# Sheet1.net
KiCad netlist of a schematic drawn in Altium Designer
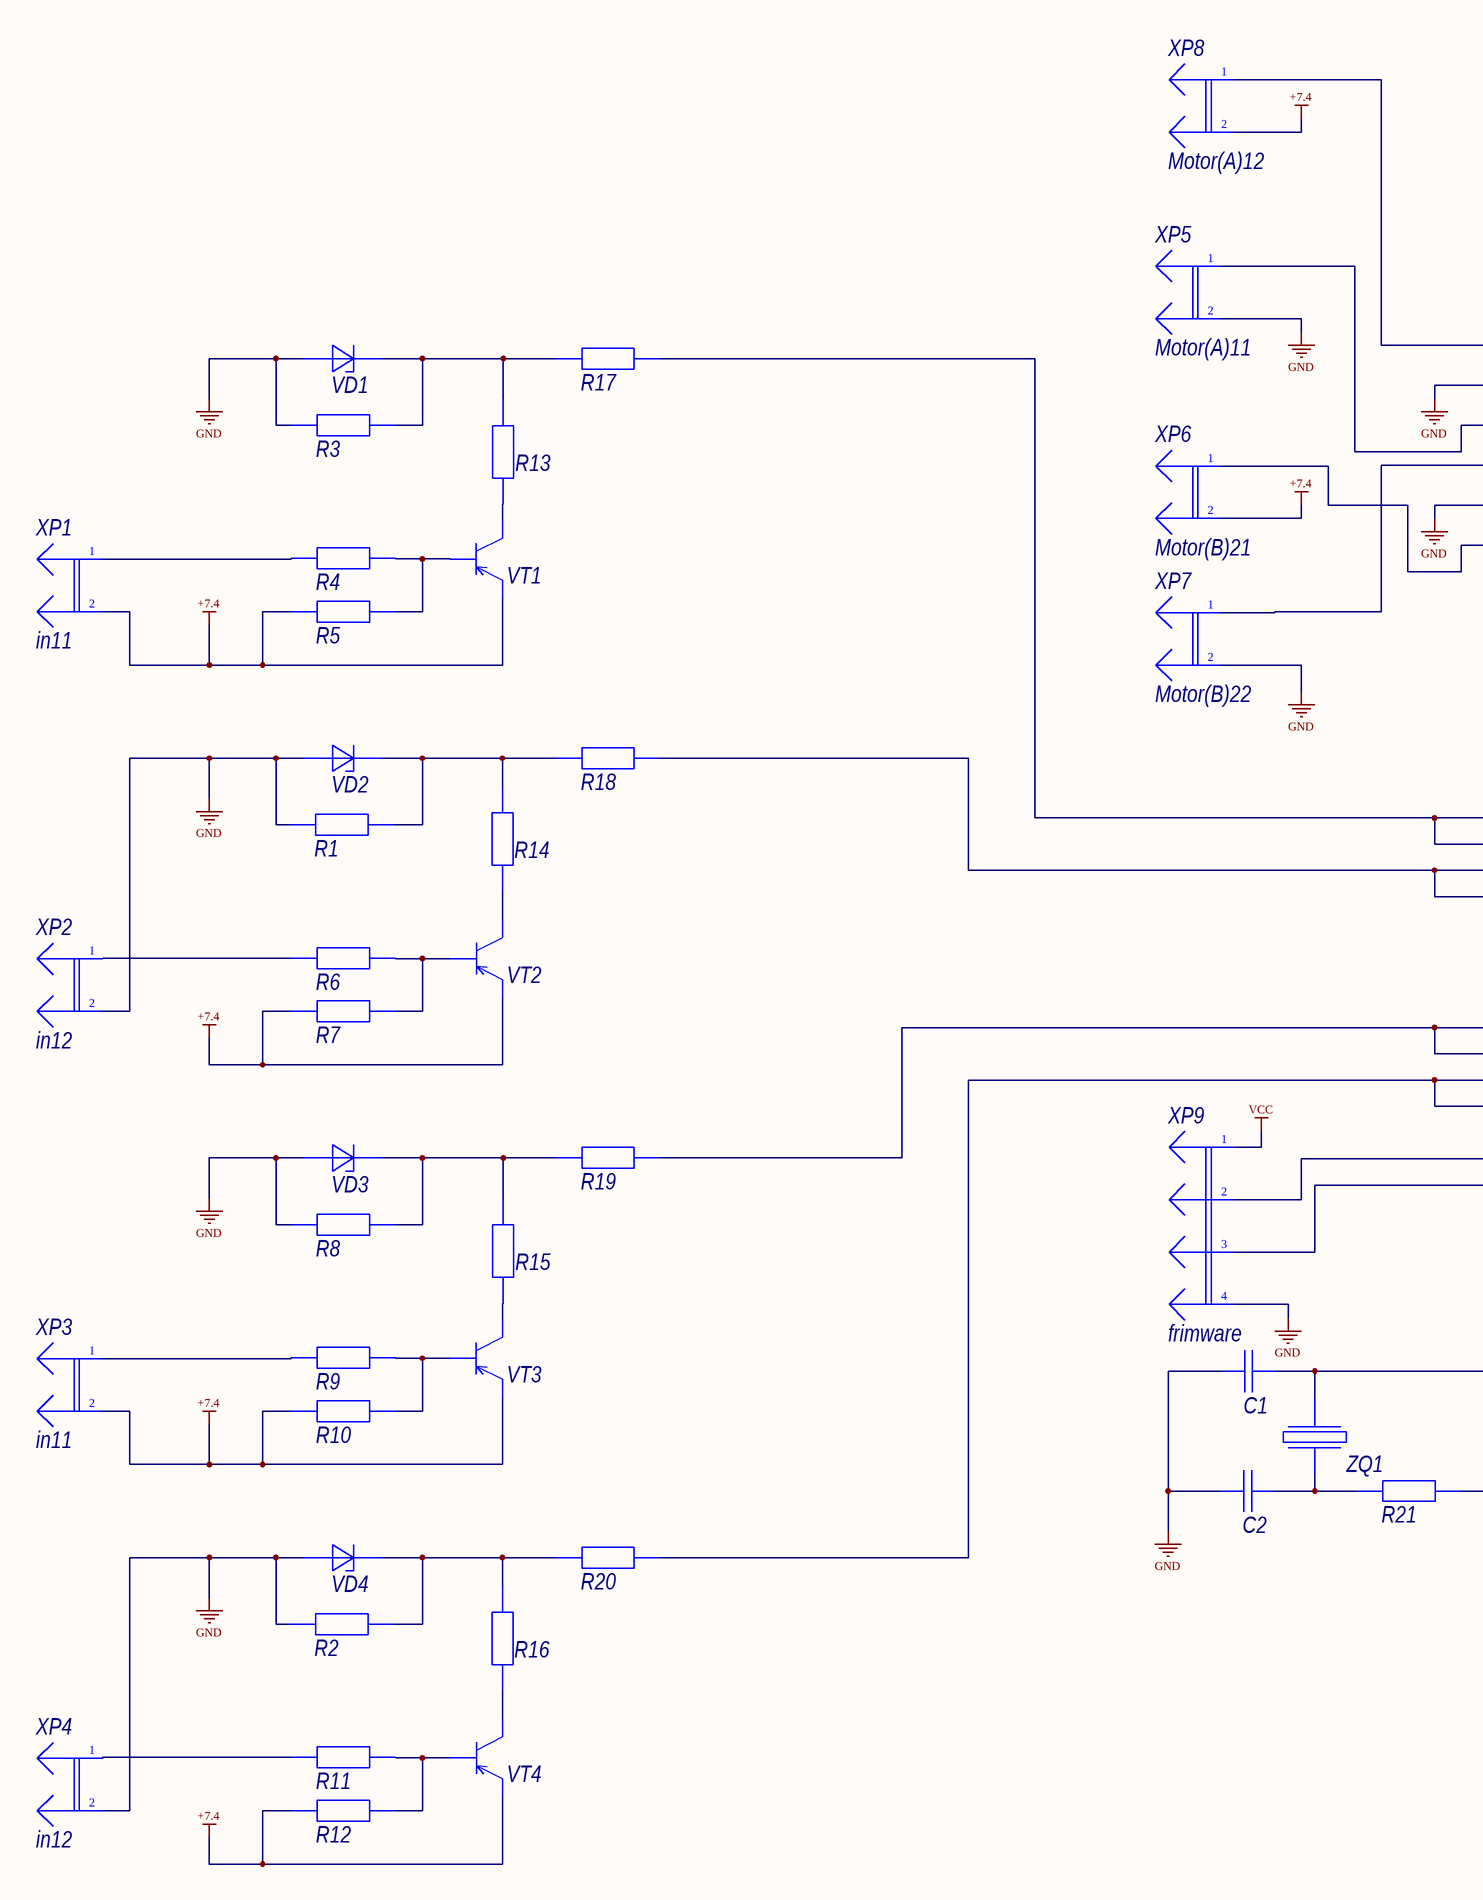
[diagram p0: Sheet1.SchDoc, left]
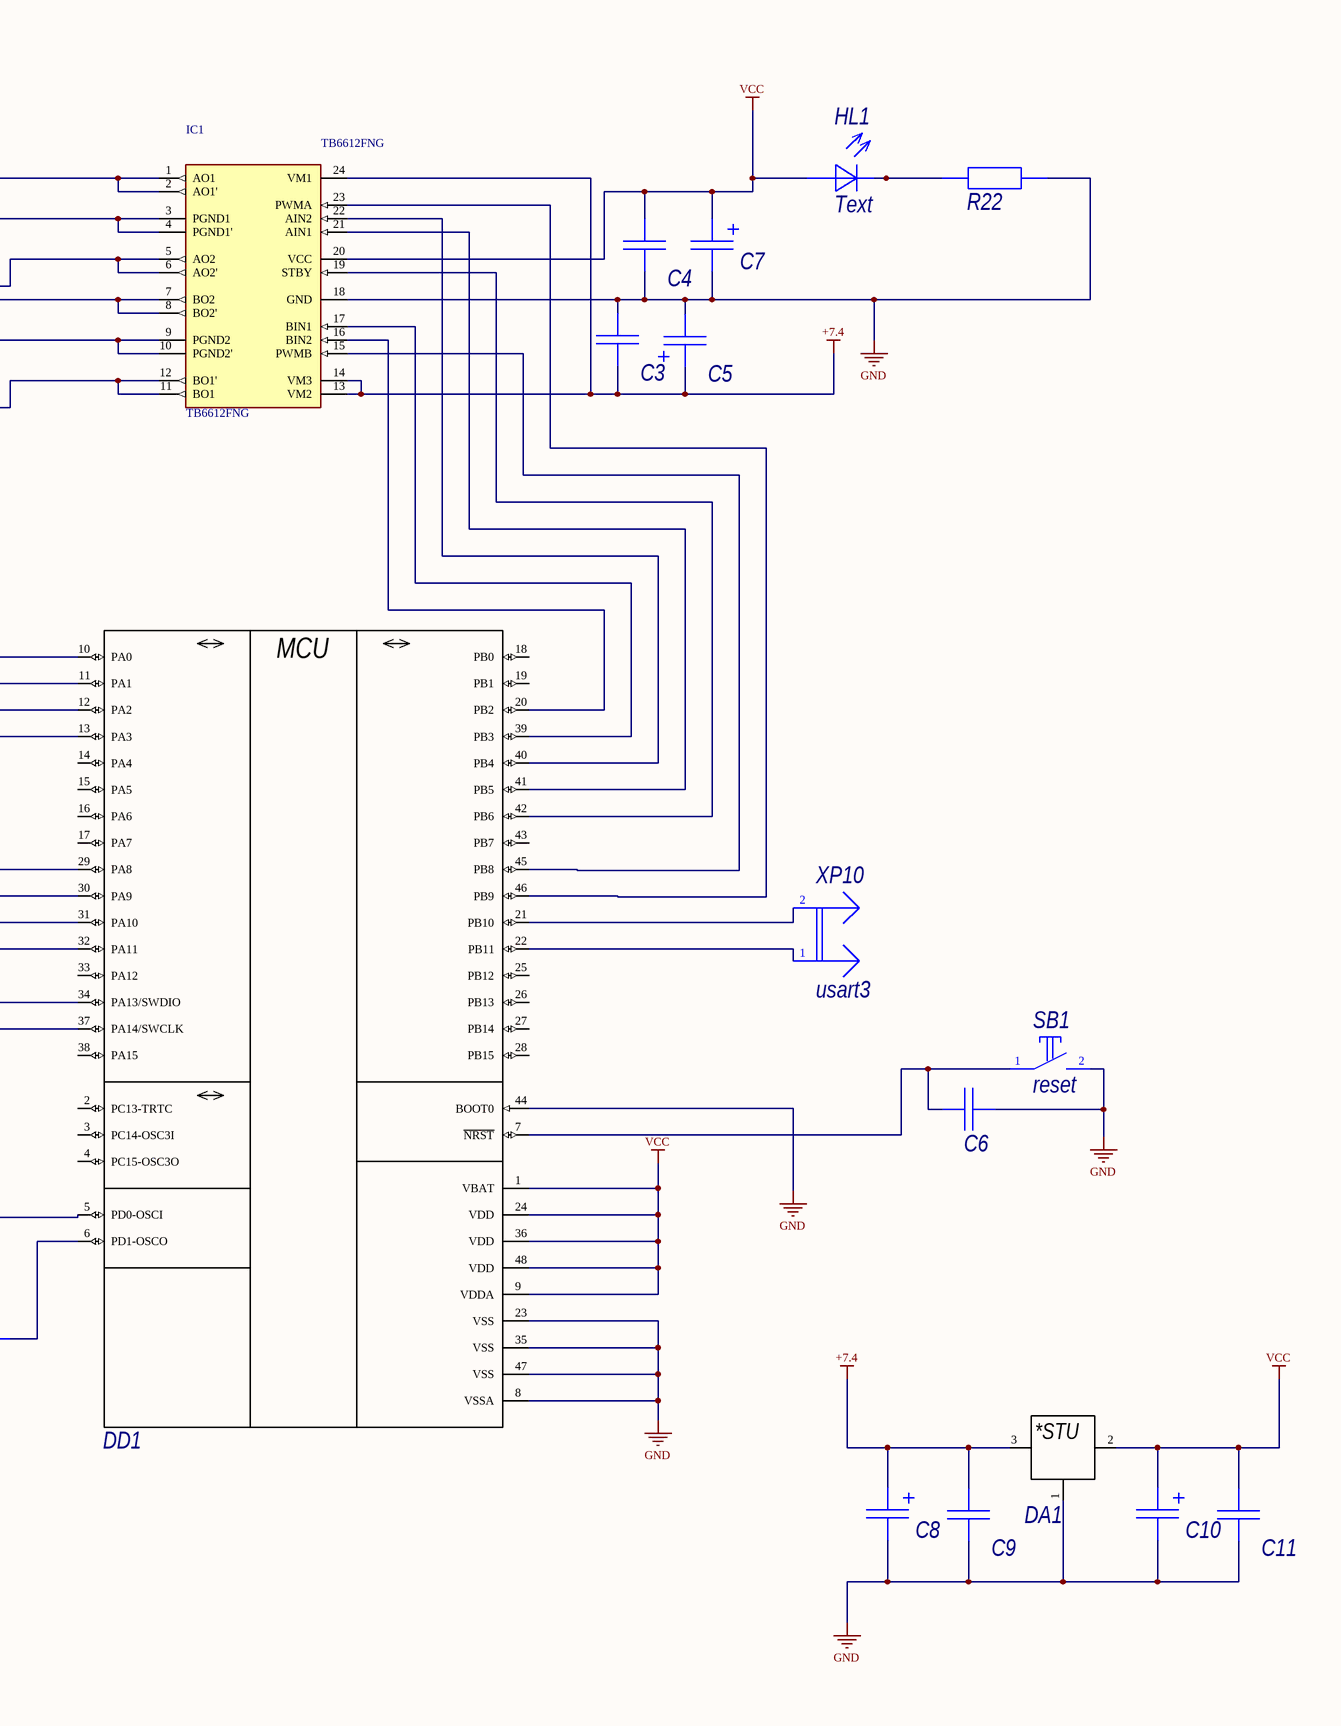
[diagram p1: Sheet1.SchDoc, right]

(export (version "E")
  (design (tool "Eeschema 10.0.6"))
  (components
    (comp (ref "C1")
      (value "Capacitor")
      (footprint "C0603")
      (description "30pF 0603")
      (fields
        (field (name "PART NUMBER") "GRM1885C1H300FA01D")
        (field (name "VOLTAGE") "50V")
        (field (name "PUBLISHER") "Andrew Danich")
      )
      (libsource (lib "Lib_IMP_GOST") (part "Capacitor"))
    )
    (comp (ref "C2")
      (value "Capacitor")
      (footprint "C0603")
      (description "30pF 0603")
      (fields
        (field (name "PART NUMBER") "GRM1885C1H300FA01D")
        (field (name "VOLTAGE") "50V")
        (field (name "PUBLISHER") "Andrew Danich")
      )
      (libsource (lib "Lib_IMP_GOST") (part "Capacitor"))
    )
    (comp (ref "C3")
      (value "Capacitor")
      (footprint "C0603")
      (description "0.1 uF")
      (fields
        (field (name "PART NUMBER") "GRM188R71C104KA01D")
        (field (name "VOLTAGE") "16V")
        (field (name "PUBLISHER") "Andrew Danich")
      )
      (libsource (lib "Lib_IMP_GOST") (part "Capacitor"))
    )
    (comp (ref "C4")
      (value "Capacitor")
      (footprint "C0603")
      (description "0.1 uF")
      (fields
        (field (name "PART NUMBER") "GRM188R71C104KA01D")
        (field (name "VOLTAGE") "16V")
        (field (name "PUBLISHER") "Andrew Danich")
      )
      (libsource (lib "Lib_IMP_GOST") (part "Capacitor"))
    )
    (comp (ref "C5")
      (value "Capacitor-T")
      (footprint "C3216-p")
      (description "10 uF")
      (fields
        (field (name "PART NUMBER") "T491A106K006AT")
        (field (name "VOLTAGE") "6.3V")
        (field (name "PUBLISHER") "Andrew Danich")
      )
      (libsource (lib "Lib_IMP_GOST") (part "Capacitor-T"))
    )
    (comp (ref "C6")
      (value "Capacitor")
      (footprint "C0603")
      (description "0.1 uF 0603")
      (fields
        (field (name "PART NUMBER") "GRM188R71C104KA01D")
        (field (name "VOLTAGE") "16V")
        (field (name "PUBLISHER") "Andrew Danich")
      )
      (libsource (lib "Lib_IMP_GOST") (part "Capacitor"))
    )
    (comp (ref "C7")
      (value "Capacitor-T")
      (footprint "C3216-p")
      (description "10 uF")
      (fields
        (field (name "PART NUMBER") "T491A106K006AT")
        (field (name "VOLTAGE") "6.3V")
        (field (name "PUBLISHER") "Andrew Danich")
      )
      (libsource (lib "Lib_IMP_GOST") (part "Capacitor-T"))
    )
    (comp (ref "C8")
      (value "Capacitor-T")
      (footprint "C3216-p")
      (description "10 uF")
      (fields
        (field (name "PART NUMBER") "T491A106K006AT")
        (field (name "VOLTAGE") "6.3V")
        (field (name "PUBLISHER") "Andrew Danich")
      )
      (libsource (lib "Lib_IMP_GOST") (part "Capacitor-T"))
    )
    (comp (ref "C9")
      (value "Capacitor")
      (footprint "C0603")
      (description "0.1 uF")
      (fields
        (field (name "PART NUMBER") "GRM188R71C104KA01D")
        (field (name "VOLTAGE") "16V")
        (field (name "PUBLISHER") "Andrew Danich")
      )
      (libsource (lib "Lib_IMP_GOST") (part "Capacitor"))
    )
    (comp (ref "C10")
      (value "Capacitor-T")
      (footprint "C3216-p")
      (description "10 uF")
      (fields
        (field (name "PART NUMBER") "T491A106K006AT")
        (field (name "VOLTAGE") "6.3V")
        (field (name "PUBLISHER") "Andrew Danich")
      )
      (libsource (lib "Lib_IMP_GOST") (part "Capacitor-T"))
    )
    (comp (ref "C11")
      (value "Capacitor")
      (footprint "C0603")
      (description "0.1 uF")
      (fields
        (field (name "PART NUMBER") "GRM188R71C104KA01D")
        (field (name "VOLTAGE") "16V")
        (field (name "PUBLISHER") "Andrew Danich")
      )
      (libsource (lib "Lib_IMP_GOST") (part "Capacitor"))
    )
    (comp (ref "DA1")
      (value "LM1117-Series")
      (footprint "SOT-223")
      (fields (field (name "PART NUMBER") "LM1117MPX-ADJ") (field (name "PUBLISHER") "Andrew Danich"))
      (libsource (lib "Lib_IMP_GOST") (part "LM1117-Series"))
    )
    (comp (ref "DD1")
      (value "STM32F103Cxxx-Series")
      (footprint "LQFP-48")
      (fields
        (field (name "PART NUMBER") "STM32F103C8T6")
        (field (name "MANUFACTURER") "STMicroelectronics")
        (field (name "PUBLISHER") "Andrew Danich")
      )
      (libsource (lib "Lib_IMP_GOST") (part "STM32F103Cxxx-Series"))
    )
    (comp (ref "HL1")
      (value "Text")
      (footprint "LD0805")
      (fields
        (field (name "PART NUMBER") "KP-2012SGC")
        (field (name "MANUFACTURER") "Kingbright")
        (field (name "PUBLISHER") "Andrew Danich")
      )
      (libsource (lib "Lib_IMP_GOST") (part "Led-1"))
    )
    (comp (ref "IC1")
      (value "TB6612FNG")
      (footprint "SSOP24")
      (description "Motor Driver Power MOSFET Parallel 24-SSOP")
      (fields (field (name "MF") "Toshiba"))
      (libsource (lib "TB6612FNG") (part "TB6612FNG"))
    )
    (comp (ref "R1")
      (value "Resistor")
      (footprint "R0402")
      (description "10k")
      (fields
        (field (name "PART NUMBER") "RC0402FR-07100KL")
        (field (name "TOLERANCE") "±1%")
        (field (name "PUBLISHER") "Andrew Danich")
      )
      (libsource (lib "Lib_IMP_GOST") (part "Resistor"))
    )
    (comp (ref "R2")
      (value "Resistor")
      (footprint "R0402")
      (description "10k")
      (fields
        (field (name "PART NUMBER") "RC0402FR-07100KL")
        (field (name "TOLERANCE") "±1%")
        (field (name "PUBLISHER") "Andrew Danich")
      )
      (libsource (lib "Lib_IMP_GOST") (part "Resistor"))
    )
    (comp (ref "R3")
      (value "Resistor")
      (footprint "R0603")
      (description "10K")
      (fields
        (field (name "PART NUMBER") "RC0603JR-0710KL")
        (field (name "TOLERANCE") "±5%")
        (field (name "PUBLISHER") "Andrew Danich")
      )
      (libsource (lib "Lib_IMP_GOST") (part "Resistor"))
    )
    (comp (ref "R4")
      (value "Resistor")
      (footprint "R0603")
      (description "10K")
      (fields
        (field (name "PART NUMBER") "RC0603JR-0710KL")
        (field (name "TOLERANCE") "±5%")
        (field (name "PUBLISHER") "Andrew Danich")
      )
      (libsource (lib "Lib_IMP_GOST") (part "Resistor"))
    )
    (comp (ref "R5")
      (value "Resistor")
      (footprint "R0603")
      (description "100k")
      (fields
        (field (name "PART NUMBER") "RC0603JR-07100KL")
        (field (name "TOLERANCE") "±5%")
        (field (name "PUBLISHER") "Andrew Danich")
      )
      (libsource (lib "Lib_IMP_GOST") (part "Resistor"))
    )
    (comp (ref "R6")
      (value "Resistor")
      (footprint "R0603")
      (description "10K")
      (fields
        (field (name "PART NUMBER") "RC0603JR-0710KL")
        (field (name "TOLERANCE") "±5%")
        (field (name "PUBLISHER") "Andrew Danich")
      )
      (libsource (lib "Lib_IMP_GOST") (part "Resistor"))
    )
    (comp (ref "R7")
      (value "Resistor")
      (footprint "R0603")
      (description "10K")
      (fields
        (field (name "PART NUMBER") "RC0603JR-0710KL")
        (field (name "TOLERANCE") "±5%")
        (field (name "PUBLISHER") "Andrew Danich")
      )
      (libsource (lib "Lib_IMP_GOST") (part "Resistor"))
    )
    (comp (ref "R8")
      (value "Resistor")
      (footprint "R0603")
      (description "10K")
      (fields
        (field (name "PART NUMBER") "RC0603JR-0710KL")
        (field (name "TOLERANCE") "±5%")
        (field (name "PUBLISHER") "Andrew Danich")
      )
      (libsource (lib "Lib_IMP_GOST") (part "Resistor"))
    )
    (comp (ref "R9")
      (value "Resistor")
      (footprint "R0603")
      (description "10K")
      (fields
        (field (name "PART NUMBER") "RC0603JR-0710KL")
        (field (name "TOLERANCE") "±5%")
        (field (name "PUBLISHER") "Andrew Danich")
      )
      (libsource (lib "Lib_IMP_GOST") (part "Resistor"))
    )
    (comp (ref "R10")
      (value "Resistor")
      (footprint "R0603")
      (description "100k")
      (fields
        (field (name "PART NUMBER") "RC0603JR-07100KL")
        (field (name "TOLERANCE") "±5%")
        (field (name "PUBLISHER") "Andrew Danich")
      )
      (libsource (lib "Lib_IMP_GOST") (part "Resistor"))
    )
    (comp (ref "R11")
      (value "Resistor")
      (footprint "R0603")
      (description "10K")
      (fields
        (field (name "PART NUMBER") "RC0603JR-0710KL")
        (field (name "TOLERANCE") "±5%")
        (field (name "PUBLISHER") "Andrew Danich")
      )
      (libsource (lib "Lib_IMP_GOST") (part "Resistor"))
    )
    (comp (ref "R12")
      (value "Resistor")
      (footprint "R0603")
      (description "10K")
      (fields
        (field (name "PART NUMBER") "RC0603JR-0710KL")
        (field (name "TOLERANCE") "±5%")
        (field (name "PUBLISHER") "Andrew Danich")
      )
      (libsource (lib "Lib_IMP_GOST") (part "Resistor"))
    )
    (comp (ref "R13")
      (value "Resistor")
      (footprint "R0603")
      (description "1k")
      (fields
        (field (name "PART NUMBER") "RC0603JR-071KL")
        (field (name "TOLERANCE") "±5%")
        (field (name "PUBLISHER") "Andrew Danich")
      )
      (libsource (lib "Lib_IMP_GOST") (part "Resistor"))
    )
    (comp (ref "R14")
      (value "Resistor")
      (footprint "R0603")
      (description "1k")
      (fields
        (field (name "PART NUMBER") "RC0603JR-071KL")
        (field (name "TOLERANCE") "±5%")
        (field (name "PUBLISHER") "Andrew Danich")
      )
      (libsource (lib "Lib_IMP_GOST") (part "Resistor"))
    )
    (comp (ref "R15")
      (value "Resistor")
      (footprint "R0603")
      (description "1k")
      (fields
        (field (name "PART NUMBER") "RC0603JR-071KL")
        (field (name "TOLERANCE") "±5%")
        (field (name "PUBLISHER") "Andrew Danich")
      )
      (libsource (lib "Lib_IMP_GOST") (part "Resistor"))
    )
    (comp (ref "R16")
      (value "Resistor")
      (footprint "R0603")
      (description "1k")
      (fields
        (field (name "PART NUMBER") "RC0603JR-071KL")
        (field (name "TOLERANCE") "±5%")
        (field (name "PUBLISHER") "Andrew Danich")
      )
      (libsource (lib "Lib_IMP_GOST") (part "Resistor"))
    )
    (comp (ref "R17")
      (value "Resistor")
      (footprint "R0603")
      (description "1k")
      (fields
        (field (name "PART NUMBER") "RC0603JR-071KL")
        (field (name "TOLERANCE") "±5%")
        (field (name "PUBLISHER") "Andrew Danich")
      )
      (libsource (lib "Lib_IMP_GOST") (part "Resistor"))
    )
    (comp (ref "R18")
      (value "Resistor")
      (footprint "R0603")
      (description "1k")
      (fields
        (field (name "PART NUMBER") "RC0603JR-071KL")
        (field (name "TOLERANCE") "±5%")
        (field (name "PUBLISHER") "Andrew Danich")
      )
      (libsource (lib "Lib_IMP_GOST") (part "Resistor"))
    )
    (comp (ref "R19")
      (value "Resistor")
      (footprint "R0603")
      (description "1k")
      (fields
        (field (name "PART NUMBER") "RC0603JR-071KL")
        (field (name "TOLERANCE") "±5%")
        (field (name "PUBLISHER") "Andrew Danich")
      )
      (libsource (lib "Lib_IMP_GOST") (part "Resistor"))
    )
    (comp (ref "R20")
      (value "Resistor")
      (footprint "R0603")
      (description "1k")
      (fields
        (field (name "PART NUMBER") "RC0603JR-071KL")
        (field (name "TOLERANCE") "±5%")
        (field (name "PUBLISHER") "Andrew Danich")
      )
      (libsource (lib "Lib_IMP_GOST") (part "Resistor"))
    )
    (comp (ref "R21")
      (value "Resistor")
      (footprint "R0603")
      (description "200 kOm")
      (fields
        (field (name "PART NUMBER") "RC0603FR-07200KL")
        (field (name "TOLERANCE") "±1%")
        (field (name "PUBLISHER") "Andrew Danich")
      )
      (libsource (lib "Lib_IMP_GOST") (part "Resistor"))
    )
    (comp (ref "R22")
      (value "Resistor")
      (footprint "R0805")
      (fields
        (field (name "PART NUMBER") "RC0805JR-0768RL")
        (field (name "TOLERANCE") "±5%")
        (field (name "MANUFACTURER") "Yageo")
        (field (name "PUBLISHER") "Andrew Danich")
      )
      (libsource (lib "Lib_IMP_GOST") (part "Resistor"))
    )
    (comp (ref "SB1")
      (value "reset")
      (footprint "DTS-32")
      (fields (field (name "PART NUMBER") "DTS-32") (field (name "PUBLISHER") "Andrew Danich"))
      (libsource (lib "Lib_IMP_GOST") (part "BT-01x-01p"))
    )
    (comp (ref "VD1")
      (value "Zener")
      (footprint "SOT-23")
      (fields
        (field (name "PART NUMBER") "BZX84-C3V3")
        (field (name "MANUFACTURER") "NXP")
        (field (name "PUBLISHER") "Andrew Danich")
      )
      (libsource (lib "Lib_IMP_GOST") (part "Zener"))
    )
    (comp (ref "VD2")
      (value "Zener")
      (footprint "SOT-23")
      (fields
        (field (name "PART NUMBER") "BZX84-C3V3")
        (field (name "MANUFACTURER") "NXP")
        (field (name "PUBLISHER") "Andrew Danich")
      )
      (libsource (lib "Lib_IMP_GOST") (part "Zener"))
    )
    (comp (ref "VD3")
      (value "Zener")
      (footprint "SOT-23")
      (fields
        (field (name "PART NUMBER") "BZX84-C3V3")
        (field (name "MANUFACTURER") "NXP")
        (field (name "PUBLISHER") "Andrew Danich")
      )
      (libsource (lib "Lib_IMP_GOST") (part "Zener"))
    )
    (comp (ref "VD4")
      (value "Zener")
      (footprint "SOT-23")
      (fields
        (field (name "PART NUMBER") "BZX84-C3V3")
        (field (name "MANUFACTURER") "NXP")
        (field (name "PUBLISHER") "Andrew Danich")
      )
      (libsource (lib "Lib_IMP_GOST") (part "Zener"))
    )
    (comp (ref "VT1")
      (value "BJT-PNP")
      (footprint "SOT-23")
      (fields (field (name "PART NUMBER") "BC857") (field (name "PUBLISHER") "Andrew Danich"))
      (libsource (lib "Lib_IMP_GOST") (part "BJT-PNP"))
    )
    (comp (ref "VT2")
      (value "BJT-PNP")
      (footprint "SOT-23")
      (fields (field (name "PART NUMBER") "BC857") (field (name "PUBLISHER") "Andrew Danich"))
      (libsource (lib "Lib_IMP_GOST") (part "BJT-PNP"))
    )
    (comp (ref "VT3")
      (value "BJT-PNP")
      (footprint "SOT-23")
      (fields (field (name "PART NUMBER") "BC857") (field (name "PUBLISHER") "Andrew Danich"))
      (libsource (lib "Lib_IMP_GOST") (part "BJT-PNP"))
    )
    (comp (ref "VT4")
      (value "BJT-PNP")
      (footprint "SOT-23")
      (fields (field (name "PART NUMBER") "BC857") (field (name "PUBLISHER") "Andrew Danich"))
      (libsource (lib "Lib_IMP_GOST") (part "BJT-PNP"))
    )
    (comp (ref "XP1")
      (value "in11")
      (footprint "PLS-2")
      (fields (field (name "PART NUMBER") "PLS-2") (field (name "PUBLISHER") "Andrew Danich"))
      (libsource (lib "Lib_IMP_GOST") (part "Con-2-M"))
    )
    (comp (ref "XP2")
      (value "in12")
      (footprint "PLS-2")
      (fields (field (name "PART NUMBER") "PLS-2") (field (name "PUBLISHER") "Andrew Danich"))
      (libsource (lib "Lib_IMP_GOST") (part "Con-2-M"))
    )
    (comp (ref "XP3")
      (value "in11")
      (footprint "PLS-2")
      (fields (field (name "PART NUMBER") "PLS-2") (field (name "PUBLISHER") "Andrew Danich"))
      (libsource (lib "Lib_IMP_GOST") (part "Con-2-M"))
    )
    (comp (ref "XP4")
      (value "in12")
      (footprint "PLS-2")
      (fields (field (name "PART NUMBER") "PLS-2") (field (name "PUBLISHER") "Andrew Danich"))
      (libsource (lib "Lib_IMP_GOST") (part "Con-2-M"))
    )
    (comp (ref "XP5")
      (value "Motor(A)11")
      (footprint "PLS-2")
      (fields (field (name "PART NUMBER") "PLS-2") (field (name "PUBLISHER") "Andrew Danich"))
      (libsource (lib "Lib_IMP_GOST") (part "Con-2-M"))
    )
    (comp (ref "XP6")
      (value "Motor(B)21")
      (footprint "PLS-2")
      (fields (field (name "PART NUMBER") "PLS-2") (field (name "PUBLISHER") "Andrew Danich"))
      (libsource (lib "Lib_IMP_GOST") (part "Con-2-M"))
    )
    (comp (ref "XP7")
      (value "Motor(B)22")
      (footprint "PLS-2")
      (fields (field (name "PART NUMBER") "PLS-2") (field (name "PUBLISHER") "Andrew Danich"))
      (libsource (lib "Lib_IMP_GOST") (part "Con-2-M"))
    )
    (comp (ref "XP8")
      (value "Motor(A)12")
      (footprint "PLS-2")
      (fields (field (name "PART NUMBER") "PLS-2") (field (name "PUBLISHER") "Andrew Danich"))
      (libsource (lib "Lib_IMP_GOST") (part "Con-2-M"))
    )
    (comp (ref "XP9")
      (value "frimware")
      (footprint "PLS-4RR")
      (fields (field (name "PART NUMBER") "PLS-4R") (field (name "PUBLISHER") "Andrew Danich"))
      (libsource (lib "Lib_IMP_GOST") (part "Con-4-M"))
    )
    (comp (ref "XP10")
      (value "usart3")
      (footprint "PLS-2RR")
      (fields (field (name "PART NUMBER") "PLS-2R") (field (name "PUBLISHER") "Andrew Danich"))
      (libsource (lib "Lib_IMP_GOST") (part "Con-2-M"))
    )
    (comp (ref "ZQ1")
      (value "Crystal")
      (footprint "HC-49S")
      (description "8MHz")
      (fields (field (name "PART NUMBER") "HC-49S 8MHz") (field (name "PUBLISHER") "Andrew Danich"))
      (libsource (lib "Lib_IMP_GOST") (part "Crystal"))
    )
  )
  (nets
    (net (code "1") (name "+7.4") (class "Default")
      (node (ref "C3") (pin "1") (pinfunction "1_1") (pintype "passive"))
      (node (ref "C5") (pin "1") (pinfunction "1_1") (pintype "passive"))
      (node (ref "C8") (pin "1") (pinfunction "1_1") (pintype "passive"))
      (node (ref "C9") (pin "1") (pinfunction "1_1") (pintype "passive"))
      (node (ref "DA1") (pin "3") (pinfunction "In_3") (pintype "passive"))
      (node (ref "IC1") (pin "13") (pinfunction "VM2_13") (pintype "power_in"))
      (node (ref "IC1") (pin "14") (pinfunction "VM3_14") (pintype "power_in"))
      (node (ref "IC1") (pin "24") (pinfunction "VM1_24") (pintype "power_in"))
      (node (ref "R10") (pin "1") (pinfunction "1_1") (pintype "passive"))
      (node (ref "R12") (pin "1") (pinfunction "1_1") (pintype "passive"))
      (node (ref "R5") (pin "1") (pinfunction "1_1") (pintype "passive"))
      (node (ref "R7") (pin "1") (pinfunction "1_1") (pintype "passive"))
      (node (ref "VT1") (pin "3") (pinfunction "Э_3") (pintype "passive"))
      (node (ref "VT2") (pin "3") (pinfunction "Э_3") (pintype "passive"))
      (node (ref "VT3") (pin "3") (pinfunction "Э_3") (pintype "passive"))
      (node (ref "VT4") (pin "3") (pinfunction "Э_3") (pintype "passive"))
      (node (ref "XP1") (pin "2") (pintype "passive"))
      (node (ref "XP3") (pin "2") (pintype "passive"))
      (node (ref "XP6") (pin "2") (pintype "passive"))
      (node (ref "XP8") (pin "2") (pintype "passive"))
    )
    (net (code "2") (name "GND") (class "Default")
      (node (ref "C1") (pin "1") (pinfunction "1_1") (pintype "passive"))
      (node (ref "C10") (pin "2") (pinfunction "2_2") (pintype "passive"))
      (node (ref "C11") (pin "2") (pinfunction "2_2") (pintype "passive"))
      (node (ref "C2") (pin "1") (pinfunction "1_1") (pintype "passive"))
      (node (ref "C3") (pin "2") (pinfunction "2_2") (pintype "passive"))
      (node (ref "C4") (pin "1") (pinfunction "1_1") (pintype "passive"))
      (node (ref "C5") (pin "2") (pinfunction "2_2") (pintype "passive"))
      (node (ref "C6") (pin "2") (pinfunction "2_2") (pintype "passive"))
      (node (ref "C7") (pin "2") (pinfunction "2_2") (pintype "passive"))
      (node (ref "C8") (pin "2") (pinfunction "2_2") (pintype "passive"))
      (node (ref "C9") (pin "2") (pinfunction "2_2") (pintype "passive"))
      (node (ref "DA1") (pin "1") (pinfunction "Adj/GND_1") (pintype "passive"))
      (node (ref "DD1") (pin "23") (pinfunction "VSS_23") (pintype "power_in"))
      (node (ref "DD1") (pin "35") (pinfunction "VSS_35") (pintype "power_in"))
      (node (ref "DD1") (pin "44") (pinfunction "BOOT0_44") (pintype "input"))
      (node (ref "DD1") (pin "47") (pinfunction "VSS_47") (pintype "power_in"))
      (node (ref "DD1") (pin "8") (pinfunction "VSSA_8") (pintype "power_in"))
      (node (ref "IC1") (pin "10") (pinfunction "PGND2'_10") (pintype "power_in"))
      (node (ref "IC1") (pin "18") (pinfunction "GND_18") (pintype "power_in"))
      (node (ref "IC1") (pin "3") (pinfunction "PGND1_3") (pintype "power_in"))
      (node (ref "IC1") (pin "4") (pinfunction "PGND1'_4") (pintype "power_in"))
      (node (ref "IC1") (pin "9") (pinfunction "PGND2_9") (pintype "power_in"))
      (node (ref "R1") (pin "2") (pinfunction "2_2") (pintype "passive"))
      (node (ref "R2") (pin "2") (pinfunction "2_2") (pintype "passive"))
      (node (ref "R22") (pin "2") (pinfunction "2_2") (pintype "passive"))
      (node (ref "R3") (pin "1") (pinfunction "1_1") (pintype "passive"))
      (node (ref "R8") (pin "1") (pinfunction "1_1") (pintype "passive"))
      (node (ref "SB1") (pin "2") (pintype "passive"))
      (node (ref "VD1") (pin "1") (pinfunction "А_1") (pintype "passive"))
      (node (ref "VD2") (pin "1") (pinfunction "А_1") (pintype "passive"))
      (node (ref "VD3") (pin "1") (pinfunction "А_1") (pintype "passive"))
      (node (ref "VD4") (pin "1") (pinfunction "А_1") (pintype "passive"))
      (node (ref "XP2") (pin "2") (pintype "passive"))
      (node (ref "XP4") (pin "2") (pintype "passive"))
      (node (ref "XP5") (pin "2") (pintype "passive"))
      (node (ref "XP7") (pin "2") (pintype "passive"))
      (node (ref "XP9") (pin "4") (pintype "passive"))
    )
    (net (code "3") (name "Net-(C2-Pad2)") (class "Default")
      (node (ref "C2") (pin "2") (pinfunction "2_2") (pintype "passive"))
      (node (ref "R21") (pin "1") (pinfunction "1_1") (pintype "passive"))
      (node (ref "ZQ1") (pin "1") (pinfunction "1_1") (pintype "passive"))
    )
    (net (code "4") (name "Net-(DD1-PA0)") (class "Default")
      (node (ref "DD1") (pin "10") (pinfunction "PA0_10") (pintype "bidirectional"))
      (node (ref "DD1") (pin "11") (pinfunction "PA1_11") (pintype "bidirectional"))
      (node (ref "R17") (pin "1") (pinfunction "1_1") (pintype "passive"))
    )
    (net (code "5") (name "Net-(DD1-PA2)") (class "Default")
      (node (ref "DD1") (pin "12") (pinfunction "PA2_12") (pintype "bidirectional"))
      (node (ref "DD1") (pin "13") (pinfunction "PA3_13") (pintype "bidirectional"))
      (node (ref "R18") (pin "1") (pinfunction "1_1") (pintype "passive"))
    )
    (net (code "6") (name "Net-(DD1-PA8)") (class "Default")
      (node (ref "DD1") (pin "29") (pinfunction "PA8_29") (pintype "bidirectional"))
      (node (ref "DD1") (pin "30") (pinfunction "PA9_30") (pintype "bidirectional"))
      (node (ref "R19") (pin "1") (pinfunction "1_1") (pintype "passive"))
    )
    (net (code "7") (name "Net-(DD1-PA10)") (class "Default")
      (node (ref "DD1") (pin "31") (pinfunction "PA10_31") (pintype "bidirectional"))
      (node (ref "DD1") (pin "32") (pinfunction "PA11_32") (pintype "bidirectional"))
      (node (ref "R20") (pin "1") (pinfunction "1_1") (pintype "passive"))
    )
    (net (code "8") (name "Net-(DD1-PA13{slash}SWDIO)") (class "Default")
      (node (ref "DD1") (pin "34") (pinfunction "PA13/SWDIO_34") (pintype "bidirectional"))
      (node (ref "XP9") (pin "2") (pintype "passive"))
    )
    (net (code "9") (name "Net-(DD1-PA14{slash}SWCLK)") (class "Default")
      (node (ref "DD1") (pin "37") (pinfunction "PA14/SWCLK_37") (pintype "bidirectional"))
      (node (ref "XP9") (pin "3") (pintype "passive"))
    )
    (net (code "10") (name "Net-(DD1-PB2)") (class "Default")
      (node (ref "DD1") (pin "20") (pinfunction "PB2_20") (pintype "bidirectional"))
      (node (ref "IC1") (pin "16") (pinfunction "BIN2_16") (pintype "input"))
    )
    (net (code "11") (name "Net-(DD1-PB3)") (class "Default")
      (node (ref "DD1") (pin "39") (pinfunction "PB3_39") (pintype "bidirectional"))
      (node (ref "IC1") (pin "17") (pinfunction "BIN1_17") (pintype "input"))
    )
    (net (code "12") (name "Net-(DD1-PB4)") (class "Default")
      (node (ref "DD1") (pin "40") (pinfunction "PB4_40") (pintype "bidirectional"))
      (node (ref "IC1") (pin "22") (pinfunction "AIN2_22") (pintype "input"))
    )
    (net (code "13") (name "Net-(DD1-PB5)") (class "Default")
      (node (ref "DD1") (pin "41") (pinfunction "PB5_41") (pintype "bidirectional"))
      (node (ref "IC1") (pin "21") (pinfunction "AIN1_21") (pintype "input"))
    )
    (net (code "14") (name "Net-(DD1-PB6)") (class "Default")
      (node (ref "DD1") (pin "42") (pinfunction "PB6_42") (pintype "bidirectional"))
      (node (ref "IC1") (pin "19") (pinfunction "STBY_19") (pintype "input"))
    )
    (net (code "15") (name "Net-(DD1-PB8)") (class "Default")
      (node (ref "DD1") (pin "45") (pinfunction "PB8_45") (pintype "bidirectional"))
      (node (ref "IC1") (pin "15") (pinfunction "PWMB_15") (pintype "input"))
    )
    (net (code "16") (name "Net-(DD1-PB9)") (class "Default")
      (node (ref "DD1") (pin "46") (pinfunction "PB9_46") (pintype "bidirectional"))
      (node (ref "IC1") (pin "23") (pinfunction "PWMA_23") (pintype "input"))
    )
    (net (code "17") (name "Net-(DD1-PB10)") (class "Default")
      (node (ref "DD1") (pin "21") (pinfunction "PB10_21") (pintype "bidirectional"))
      (node (ref "XP10") (pin "2") (pintype "passive"))
    )
    (net (code "18") (name "Net-(DD1-PB11)") (class "Default")
      (node (ref "DD1") (pin "22") (pinfunction "PB11_22") (pintype "bidirectional"))
      (node (ref "XP10") (pin "1") (pintype "passive"))
    )
    (net (code "19") (name "Net-(DD1-PD0-OSCI)") (class "Default")
      (node (ref "C1") (pin "2") (pinfunction "2_2") (pintype "passive"))
      (node (ref "DD1") (pin "5") (pinfunction "PD0-OSCI_5") (pintype "bidirectional"))
      (node (ref "ZQ1") (pin "3") (pinfunction "3_3") (pintype "passive"))
    )
    (net (code "20") (name "Net-(DD1-PD1-OSCO)") (class "Default")
      (node (ref "DD1") (pin "6") (pinfunction "PD1-OSCO_6") (pintype "bidirectional"))
      (node (ref "R21") (pin "2") (pinfunction "2_2") (pintype "passive"))
    )
    (net (code "21") (name "Net-(DD1-~{NRST})") (class "Default")
      (node (ref "C6") (pin "1") (pinfunction "1_1") (pintype "passive"))
      (node (ref "DD1") (pin "7") (pinfunction "~{NRST}_7") (pintype "bidirectional"))
      (node (ref "SB1") (pin "1") (pintype "passive"))
    )
    (net (code "22") (name "Net-(HL1-К)") (class "Default")
      (node (ref "HL1") (pin "2") (pinfunction "К_2") (pintype "passive"))
      (node (ref "R22") (pin "1") (pinfunction "1_1") (pintype "passive"))
    )
    (net (code "23") (name "Net-(IC1-AO1')") (class "Default")
      (node (ref "IC1") (pin "1") (pinfunction "AO1_1") (pintype "output"))
      (node (ref "IC1") (pin "2") (pinfunction "AO1'_2") (pintype "output"))
      (node (ref "XP8") (pin "1") (pintype "passive"))
    )
    (net (code "24") (name "Net-(IC1-AO2')") (class "Default")
      (node (ref "IC1") (pin "5") (pinfunction "AO2_5") (pintype "output"))
      (node (ref "IC1") (pin "6") (pinfunction "AO2'_6") (pintype "output"))
      (node (ref "XP5") (pin "1") (pintype "passive"))
    )
    (net (code "25") (name "Net-(IC1-BO1')") (class "Default")
      (node (ref "IC1") (pin "11") (pinfunction "BO1_11") (pintype "output"))
      (node (ref "IC1") (pin "12") (pinfunction "BO1'_12") (pintype "output"))
      (node (ref "XP6") (pin "1") (pintype "passive"))
    )
    (net (code "26") (name "Net-(IC1-BO2')") (class "Default")
      (node (ref "IC1") (pin "7") (pinfunction "BO2_7") (pintype "output"))
      (node (ref "IC1") (pin "8") (pinfunction "BO2'_8") (pintype "output"))
      (node (ref "XP7") (pin "1") (pintype "passive"))
    )
    (net (code "27") (name "Net-(R4-Pad1)") (class "Default")
      (node (ref "R4") (pin "1") (pinfunction "1_1") (pintype "passive"))
      (node (ref "XP1") (pin "1") (pintype "passive"))
    )
    (net (code "28") (name "Net-(R6-Pad1)") (class "Default")
      (node (ref "R6") (pin "1") (pinfunction "1_1") (pintype "passive"))
      (node (ref "XP2") (pin "1") (pintype "passive"))
    )
    (net (code "29") (name "Net-(R9-Pad1)") (class "Default")
      (node (ref "R9") (pin "1") (pinfunction "1_1") (pintype "passive"))
      (node (ref "XP3") (pin "1") (pintype "passive"))
    )
    (net (code "30") (name "Net-(R11-Pad1)") (class "Default")
      (node (ref "R11") (pin "1") (pinfunction "1_1") (pintype "passive"))
      (node (ref "XP4") (pin "1") (pintype "passive"))
    )
    (net (code "31") (name "Net-(VD1-К)") (class "Default")
      (node (ref "R13") (pin "1") (pinfunction "1_1") (pintype "passive"))
      (node (ref "R17") (pin "2") (pinfunction "2_2") (pintype "passive"))
      (node (ref "R3") (pin "2") (pinfunction "2_2") (pintype "passive"))
      (node (ref "VD1") (pin "2") (pinfunction "К_2") (pintype "passive"))
    )
    (net (code "32") (name "Net-(VD2-К)") (class "Default")
      (node (ref "R1") (pin "1") (pinfunction "1_1") (pintype "passive"))
      (node (ref "R14") (pin "2") (pinfunction "2_2") (pintype "passive"))
      (node (ref "R18") (pin "2") (pinfunction "2_2") (pintype "passive"))
      (node (ref "VD2") (pin "2") (pinfunction "К_2") (pintype "passive"))
    )
    (net (code "33") (name "Net-(VD3-К)") (class "Default")
      (node (ref "R15") (pin "1") (pinfunction "1_1") (pintype "passive"))
      (node (ref "R19") (pin "2") (pinfunction "2_2") (pintype "passive"))
      (node (ref "R8") (pin "2") (pinfunction "2_2") (pintype "passive"))
      (node (ref "VD3") (pin "2") (pinfunction "К_2") (pintype "passive"))
    )
    (net (code "34") (name "Net-(VD4-К)") (class "Default")
      (node (ref "R16") (pin "2") (pinfunction "2_2") (pintype "passive"))
      (node (ref "R2") (pin "1") (pinfunction "1_1") (pintype "passive"))
      (node (ref "R20") (pin "2") (pinfunction "2_2") (pintype "passive"))
      (node (ref "VD4") (pin "2") (pinfunction "К_2") (pintype "passive"))
    )
    (net (code "35") (name "Net-(VT1-Б)") (class "Default")
      (node (ref "R4") (pin "2") (pinfunction "2_2") (pintype "passive"))
      (node (ref "R5") (pin "2") (pinfunction "2_2") (pintype "passive"))
      (node (ref "VT1") (pin "1") (pinfunction "Б_1") (pintype "passive"))
    )
    (net (code "36") (name "Net-(VT1-К)") (class "Default")
      (node (ref "R13") (pin "2") (pinfunction "2_2") (pintype "passive"))
      (node (ref "VT1") (pin "2") (pinfunction "К_2") (pintype "passive"))
    )
    (net (code "37") (name "Net-(VT2-Б)") (class "Default")
      (node (ref "R6") (pin "2") (pinfunction "2_2") (pintype "passive"))
      (node (ref "R7") (pin "2") (pinfunction "2_2") (pintype "passive"))
      (node (ref "VT2") (pin "1") (pinfunction "Б_1") (pintype "passive"))
    )
    (net (code "38") (name "Net-(VT2-К)") (class "Default")
      (node (ref "R14") (pin "1") (pinfunction "1_1") (pintype "passive"))
      (node (ref "VT2") (pin "2") (pinfunction "К_2") (pintype "passive"))
    )
    (net (code "39") (name "Net-(VT3-Б)") (class "Default")
      (node (ref "R10") (pin "2") (pinfunction "2_2") (pintype "passive"))
      (node (ref "R9") (pin "2") (pinfunction "2_2") (pintype "passive"))
      (node (ref "VT3") (pin "1") (pinfunction "Б_1") (pintype "passive"))
    )
    (net (code "40") (name "Net-(VT3-К)") (class "Default")
      (node (ref "R15") (pin "2") (pinfunction "2_2") (pintype "passive"))
      (node (ref "VT3") (pin "2") (pinfunction "К_2") (pintype "passive"))
    )
    (net (code "41") (name "Net-(VT4-Б)") (class "Default")
      (node (ref "R11") (pin "2") (pinfunction "2_2") (pintype "passive"))
      (node (ref "R12") (pin "2") (pinfunction "2_2") (pintype "passive"))
      (node (ref "VT4") (pin "1") (pinfunction "Б_1") (pintype "passive"))
    )
    (net (code "42") (name "Net-(VT4-К)") (class "Default")
      (node (ref "R16") (pin "1") (pinfunction "1_1") (pintype "passive"))
      (node (ref "VT4") (pin "2") (pinfunction "К_2") (pintype "passive"))
    )
    (net (code "43") (name "VCC") (class "Default")
      (node (ref "C10") (pin "1") (pinfunction "1_1") (pintype "passive"))
      (node (ref "C11") (pin "1") (pinfunction "1_1") (pintype "passive"))
      (node (ref "C4") (pin "2") (pinfunction "2_2") (pintype "passive"))
      (node (ref "C7") (pin "1") (pinfunction "1_1") (pintype "passive"))
      (node (ref "DA1") (pin "2") (pinfunction "Out_2") (pintype "passive"))
      (node (ref "DD1") (pin "1") (pinfunction "VBAT_1") (pintype "power_in"))
      (node (ref "DD1") (pin "24") (pinfunction "VDD_24") (pintype "power_in"))
      (node (ref "DD1") (pin "36") (pinfunction "VDD_36") (pintype "power_in"))
      (node (ref "DD1") (pin "48") (pinfunction "VDD_48") (pintype "power_in"))
      (node (ref "DD1") (pin "9") (pinfunction "VDDA_9") (pintype "power_in"))
      (node (ref "HL1") (pin "1") (pinfunction "А_1") (pintype "passive"))
      (node (ref "IC1") (pin "20") (pinfunction "VCC_20") (pintype "power_in"))
      (node (ref "XP9") (pin "1") (pintype "passive"))
    )
    (net (code "44") (name "unconnected-(DD1-PA4-Pad14)") (class "Default")
      (node (ref "DD1") (pin "14") (pinfunction "PA4_14") (pintype "bidirectional"))
    )
    (net (code "45") (name "unconnected-(DD1-PA5-Pad15)") (class "Default")
      (node (ref "DD1") (pin "15") (pinfunction "PA5_15") (pintype "bidirectional"))
    )
    (net (code "46") (name "unconnected-(DD1-PA6-Pad16)") (class "Default")
      (node (ref "DD1") (pin "16") (pinfunction "PA6_16") (pintype "bidirectional"))
    )
    (net (code "47") (name "unconnected-(DD1-PA7-Pad17)") (class "Default")
      (node (ref "DD1") (pin "17") (pinfunction "PA7_17") (pintype "bidirectional"))
    )
    (net (code "48") (name "unconnected-(DD1-PA12-Pad33)") (class "Default")
      (node (ref "DD1") (pin "33") (pinfunction "PA12_33") (pintype "bidirectional"))
    )
    (net (code "49") (name "unconnected-(DD1-PA15-Pad38)") (class "Default")
      (node (ref "DD1") (pin "38") (pinfunction "PA15_38") (pintype "bidirectional"))
    )
    (net (code "50") (name "unconnected-(DD1-PB0-Pad18)") (class "Default")
      (node (ref "DD1") (pin "18") (pinfunction "PB0_18") (pintype "bidirectional"))
    )
    (net (code "51") (name "unconnected-(DD1-PB1-Pad19)") (class "Default")
      (node (ref "DD1") (pin "19") (pinfunction "PB1_19") (pintype "bidirectional"))
    )
    (net (code "52") (name "unconnected-(DD1-PB7-Pad43)") (class "Default")
      (node (ref "DD1") (pin "43") (pinfunction "PB7_43") (pintype "bidirectional"))
    )
    (net (code "53") (name "unconnected-(DD1-PB12-Pad25)") (class "Default")
      (node (ref "DD1") (pin "25") (pinfunction "PB12_25") (pintype "bidirectional"))
    )
    (net (code "54") (name "unconnected-(DD1-PB13-Pad26)") (class "Default")
      (node (ref "DD1") (pin "26") (pinfunction "PB13_26") (pintype "bidirectional"))
    )
    (net (code "55") (name "unconnected-(DD1-PB14-Pad27)") (class "Default")
      (node (ref "DD1") (pin "27") (pinfunction "PB14_27") (pintype "bidirectional"))
    )
    (net (code "56") (name "unconnected-(DD1-PB15-Pad28)") (class "Default")
      (node (ref "DD1") (pin "28") (pinfunction "PB15_28") (pintype "bidirectional"))
    )
    (net (code "57") (name "unconnected-(DD1-PC13-TRTC-Pad2)") (class "Default")
      (node (ref "DD1") (pin "2") (pinfunction "PC13-TRTC_2") (pintype "bidirectional"))
    )
    (net (code "58") (name "unconnected-(DD1-PC14-OSC3I-Pad3)") (class "Default")
      (node (ref "DD1") (pin "3") (pinfunction "PC14-OSC3I_3") (pintype "bidirectional"))
    )
    (net (code "59") (name "unconnected-(DD1-PC15-OSC3O-Pad4)") (class "Default")
      (node (ref "DD1") (pin "4") (pinfunction "PC15-OSC3O_4") (pintype "bidirectional"))
    )
  )
)
